# Stepper_Motor_Driver.net
KiCad netlist of a schematic drawn in Altium Designer
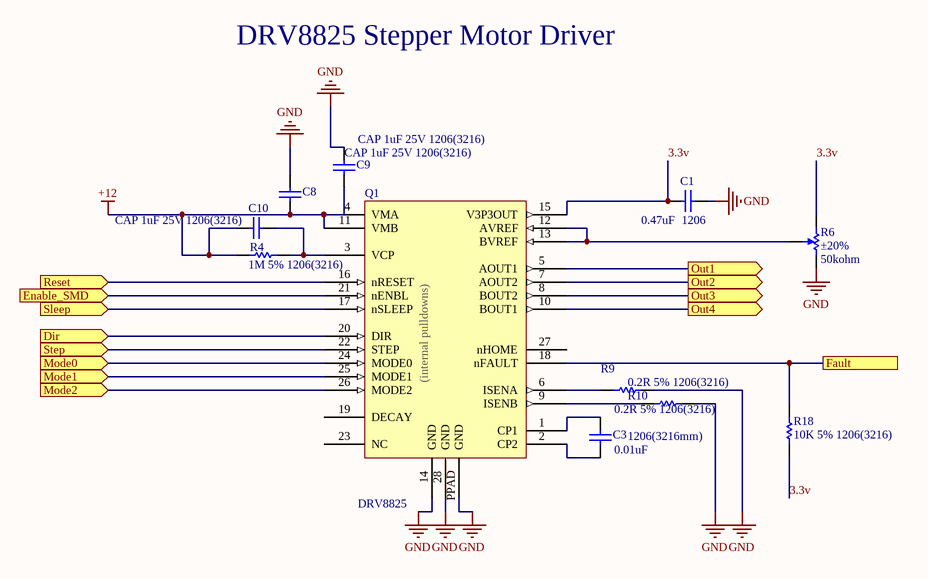
[diagram p0: Stepper Motor Driver.SchDoc]

(export (version "E")
  (design (tool "Eeschema 10.0.6"))
  (components
    (comp (ref "C1")
      (value "1206C474K5RACTU")
      (footprint "CAPC3216X100X50NL20T25")
      (description "Chip Capacitor, 470 nF, +/- 10%, 50 V, -55 to 125 degC, 1206 (3216 Metric), RoHS, Tape and Reel")
      (fields
        (field (name "MANUFACTURER") "Kemet")
        (field (name "CAPACITANCE") "0.47uF")
        (field (name "PACKAGE REFERENCE") "1206")
        (field (name "TOLERANCE") "10%")
      )
      (libsource (lib "Altium Content Vault") (part "CAP-NP-2"))
    )
    (comp (ref "C3")
      (value "C1206C103K5RACTU")
      (footprint "KEMT-1206-2_L")
      (fields
        (field (name "CASE SIZE") "1206(3216mm)")
        (field (name "MANUFACTURER") "Kemet")
        (field (name "CAPACITANCE") "0.01uF")
        (field (name "TOLERANCE") "10%")
      )
      (libsource (lib "Altium Content Vault") (part "CAP-NP-2"))
    )
    (comp (ref "C8")
      (value "CAP 1uF 25V 1206(3216)")
      (footprint "CAPC1206(3216)170_M")
      (description "CAP 1uF 25V ±10% 1206 (3216 Metric) Thickness 1.7mm SMD")
      (fields (field (name "TOLERANCE") "Â±10%"))
      (libsource (lib "Altium Content Vault") (part "CAP"))
    )
    (comp (ref "C9")
      (value "CAP 1uF 25V 1206(3216)")
      (footprint "CAPC1206(3216)170_M")
      (description "CAP 1uF 25V ±10% 1206 (3216 Metric) Thickness 1.7mm SMD")
      (fields (field (name "TOLERANCE") "Â±10%"))
      (libsource (lib "Altium Content Vault") (part "CAP"))
    )
    (comp (ref "C10")
      (value "CAP 1uF 25V 1206(3216)")
      (footprint "CAPC1206(3216)170_M")
      (description "CAP 1uF 25V ±10% 1206 (3216 Metric) Thickness 1.7mm SMD")
      (fields (field (name "TOLERANCE") "Â±10%"))
      (libsource (lib "Altium Content Vault") (part "CAP"))
    )
    (comp (ref "Q1")
      (value "DRV8825")
      (footprint "DRV8825 HTSSOP")
      (description "TI DRV8825 Stepper Motor Controller IC")
      (libsource (lib "JCULibrary_AS2 (1)") (part "Stepper motor driver DRV8825"))
    )
    (comp (ref "R4")
      (value "1M 5% 1206(3216)")
      (footprint "RESC1206(3216)_L")
      (description "1M 0.25W 5% 1206 (3216 Metric)  SMD")
      (fields (field (name "POWER") "0.25 W") (field (name "TOLERANCE") "5 %"))
      (libsource (lib "Altium Content Vault") (part "RES"))
    )
    (comp (ref "R6")
      (value "3313J-1-503E")
      (footprint "BOUR-3313J-1_V")
      (fields
        (field (name "MANUFACTURER") "Bourns")
        (field (name "RESISTANCE TOLERANCE") "±20%")
        (field (name "TRACK RESISTANCE") "50kohm")
      )
      (libsource (lib "Altium Content Vault") (part "RES-ADJ-3_A"))
    )
    (comp (ref "R9")
      (value "0.2R 5% 1206(3216)")
      (footprint "RESC1206(3216)_L")
      (description "0.2R 0.25W 5% 1206 (3216 Metric)  SMD")
      (fields (field (name "TOLERANCE") "5 %") (field (name "POWER") "0.25 W"))
      (libsource (lib "Altium Content Vault") (part "RES"))
    )
    (comp (ref "R10")
      (value "0.2R 5% 1206(3216)")
      (footprint "RESC1206(3216)_L")
      (description "0.2R 0.25W 5% 1206 (3216 Metric)  SMD")
      (fields (field (name "TOLERANCE") "5 %") (field (name "POWER") "0.25 W"))
      (libsource (lib "Altium Content Vault") (part "RES"))
    )
    (comp (ref "R18")
      (value "10K 5% 1206(3216)")
      (footprint "RESC1206(3216)_M")
      (description "10K 0.25W 5% 1206 (3216 Metric)  SMD")
      (fields (field (name "POWER") "0.25 W") (field (name "TOLERANCE") "5 %"))
      (libsource (lib "Altium Content Vault") (part "RES"))
    )
  )
  (nets
    (net (code "1") (name "+12") (class "Default")
      (node (ref "C10") (pin "2") (pinfunction "2_2") (pintype "passive"))
      (node (ref "C8") (pin "1") (pinfunction "1_1") (pintype "passive"))
      (node (ref "C9") (pin "1") (pinfunction "1_1") (pintype "passive"))
      (node (ref "Q1") (pin "11") (pinfunction "VMB_11") (pintype "power_in"))
      (node (ref "Q1") (pin "4") (pinfunction "VMA_4") (pintype "power_in"))
      (node (ref "R4") (pin "1") (pinfunction "1_1") (pintype "passive"))
    )
    (net (code "2") (name "/3.3v") (class "Default")
      (node (ref "C1") (pin "1") (pinfunction "1_1") (pintype "passive"))
      (node (ref "Q1") (pin "15") (pinfunction "V3P3OUT_15") (pintype "output"))
      (node (ref "R18") (pin "1") (pinfunction "1_1") (pintype "passive"))
      (node (ref "R6") (pin "1") (pinfunction "1_1") (pintype "passive"))
    )
    (net (code "3") (name "/Dir") (class "Default")
      (node (ref "Q1") (pin "20") (pinfunction "DIR_20") (pintype "input"))
    )
    (net (code "4") (name "/Enable_SMD") (class "Default")
      (node (ref "Q1") (pin "21") (pinfunction "nENBL_21") (pintype "input"))
    )
    (net (code "5") (name "/Fault") (class "Default")
      (node (ref "Q1") (pin "18") (pinfunction "nFAULT_18") (pintype "open_collector"))
      (node (ref "R18") (pin "2") (pinfunction "2_2") (pintype "passive"))
    )
    (net (code "6") (name "/Mode0") (class "Default")
      (node (ref "Q1") (pin "24") (pinfunction "MODE0_24") (pintype "input"))
    )
    (net (code "7") (name "/Mode1") (class "Default")
      (node (ref "Q1") (pin "25") (pinfunction "MODE1_25") (pintype "input"))
    )
    (net (code "8") (name "/Mode2") (class "Default")
      (node (ref "Q1") (pin "26") (pinfunction "MODE2_26") (pintype "input"))
    )
    (net (code "9") (name "/Out1") (class "Default")
      (node (ref "Q1") (pin "5") (pinfunction "AOUT1_5") (pintype "output"))
    )
    (net (code "10") (name "/Out2") (class "Default")
      (node (ref "Q1") (pin "7") (pinfunction "AOUT2_7") (pintype "output"))
    )
    (net (code "11") (name "/Out3") (class "Default")
      (node (ref "Q1") (pin "8") (pinfunction "BOUT2_8") (pintype "output"))
    )
    (net (code "12") (name "/Out4") (class "Default")
      (node (ref "Q1") (pin "10") (pinfunction "BOUT1_10") (pintype "output"))
    )
    (net (code "13") (name "/Reset") (class "Default")
      (node (ref "Q1") (pin "16") (pinfunction "nRESET_16") (pintype "input"))
    )
    (net (code "14") (name "/Sleep") (class "Default")
      (node (ref "Q1") (pin "17") (pinfunction "nSLEEP_17") (pintype "input"))
    )
    (net (code "15") (name "/Step") (class "Default")
      (node (ref "Q1") (pin "22") (pinfunction "STEP_22") (pintype "input"))
    )
    (net (code "16") (name "GND") (class "Default")
      (node (ref "C1") (pin "2") (pinfunction "2_2") (pintype "passive"))
      (node (ref "C8") (pin "2") (pinfunction "2_2") (pintype "passive"))
      (node (ref "C9") (pin "2") (pinfunction "2_2") (pintype "passive"))
      (node (ref "Q1") (pin "14") (pinfunction "GND_14") (pintype "power_in"))
      (node (ref "Q1") (pin "28") (pinfunction "GND_28") (pintype "power_in"))
      (node (ref "Q1") (pin "PPAD") (pinfunction "GND_PPAD") (pintype "power_in"))
      (node (ref "R10") (pin "2") (pinfunction "2_2") (pintype "passive"))
      (node (ref "R6") (pin "3") (pinfunction "3_3") (pintype "passive"))
      (node (ref "R9") (pin "2") (pinfunction "2_2") (pintype "passive"))
    )
    (net (code "17") (name "Net-(Q1-AVREF)") (class "Default")
      (node (ref "Q1") (pin "12") (pinfunction "AVREF_12") (pintype "input"))
      (node (ref "Q1") (pin "13") (pinfunction "BVREF_13") (pintype "input"))
      (node (ref "R6") (pin "2") (pinfunction "2_2") (pintype "passive"))
    )
    (net (code "18") (name "Net-(Q1-CP1)") (class "Default")
      (node (ref "C3") (pin "2") (pinfunction "2_2") (pintype "passive"))
      (node (ref "Q1") (pin "1") (pinfunction "CP1_1") (pintype "power_in"))
    )
    (net (code "19") (name "Net-(Q1-CP2)") (class "Default")
      (node (ref "C3") (pin "1") (pinfunction "1_1") (pintype "passive"))
      (node (ref "Q1") (pin "2") (pinfunction "CP2_2") (pintype "power_in"))
    )
    (net (code "20") (name "Net-(Q1-ISENA)") (class "Default")
      (node (ref "Q1") (pin "6") (pinfunction "ISENA_6") (pintype "output"))
      (node (ref "R9") (pin "1") (pinfunction "1_1") (pintype "passive"))
    )
    (net (code "21") (name "Net-(Q1-ISENB)") (class "Default")
      (node (ref "Q1") (pin "9") (pinfunction "ISENB_9") (pintype "output"))
      (node (ref "R10") (pin "1") (pinfunction "1_1") (pintype "passive"))
    )
    (net (code "22") (name "Net-(Q1-VCP)") (class "Default")
      (node (ref "C10") (pin "1") (pinfunction "1_1") (pintype "passive"))
      (node (ref "Q1") (pin "3") (pinfunction "VCP_3") (pintype "power_in"))
      (node (ref "R4") (pin "2") (pinfunction "2_2") (pintype "passive"))
    )
    (net (code "23") (name "unconnected-(Q1-DECAY-Pad19)") (class "Default")
      (node (ref "Q1") (pin "19") (pinfunction "DECAY_19") (pintype "passive"))
    )
    (net (code "24") (name "unconnected-(Q1-NC-Pad23)") (class "Default")
      (node (ref "Q1") (pin "23") (pinfunction "NC_23") (pintype "passive"))
    )
    (net (code "25") (name "unconnected-(Q1-nHOME-Pad27)") (class "Default")
      (node (ref "Q1") (pin "27") (pinfunction "nHOME_27") (pintype "open_collector"))
    )
  )
)
